# Arduino_Board_rev2.net
KiCad netlist of a schematic drawn in EAGLE
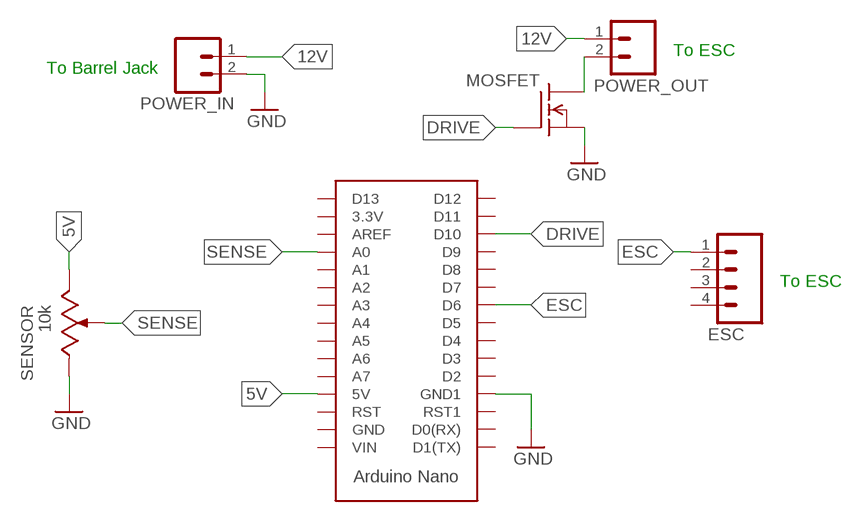
[diagram p0: schematic, sheet 1]

(export (version "E")
  (design (tool "Eeschema 10.0.6"))
  (components
    (comp (ref "ESC")
      (value "M04")
      (footprint "eagle-import:1X04")
      (libsource (lib "eagle-import") (part "M04"))
    )
    (comp (ref "MOSFET")
      (value "SI2312")
      (footprint "eagle-import:SOT-23")
      (libsource (lib "eagle-import") (part "SI2312"))
    )
    (comp (ref "POWER_IN")
      (value "M02")
      (footprint "eagle-import:1X02")
      (libsource (lib "eagle-import") (part "M02"))
    )
    (comp (ref "POWER_OUT")
      (value "M02")
      (footprint "eagle-import:1X02")
      (libsource (lib "eagle-import") (part "M02"))
    )
    (comp (ref "SENSOR")
      (value "10k")
      (footprint "eagle-import:SV03A")
      (libsource (lib "eagle-import") (part "SV03"))
    )
    (comp (ref "U$1")
      (value "ARDUINO_NANO")
      (footprint "eagle-import:ARDUINO_NANO")
      (libsource (lib "eagle-import") (part "ARDUINO_NANO"))
    )
  )
  (nets
    (net (code "1") (name "5V") (class "Default")
      (node (ref "SENSOR") (pin "3") (pinfunction "A_3") (pintype "passive"))
      (node (ref "U$1") (pin "5V") (pinfunction "5V_5V") (pintype "bidirectional"))
    )
    (net (code "2") (name "12V") (class "Default")
      (node (ref "POWER_IN") (pin "1") (pinfunction "1_1") (pintype "passive"))
      (node (ref "POWER_OUT") (pin "1") (pinfunction "1_1") (pintype "passive"))
    )
    (net (code "3") (name "DRIVE") (class "Default")
      (node (ref "MOSFET") (pin "1") (pinfunction "G_1") (pintype "passive"))
      (node (ref "U$1") (pin "D10") (pinfunction "D10_D10") (pintype "bidirectional"))
    )
    (net (code "4") (name "ESC") (class "Default")
      (node (ref "ESC") (pin "1") (pinfunction "1_1") (pintype "passive"))
      (node (ref "U$1") (pin "D6") (pinfunction "D6_D6") (pintype "bidirectional"))
    )
    (net (code "5") (name "GND") (class "Default")
      (node (ref "MOSFET") (pin "2") (pinfunction "S_2") (pintype "passive"))
      (node (ref "POWER_IN") (pin "2") (pinfunction "2_2") (pintype "passive"))
      (node (ref "SENSOR") (pin "1") (pinfunction "E_1") (pintype "passive"))
      (node (ref "U$1") (pin "GND1") (pinfunction "GND1_GND1") (pintype "bidirectional"))
    )
    (net (code "6") (name "Net-(MOSFET-D)") (class "Default")
      (node (ref "MOSFET") (pin "3") (pinfunction "D_3") (pintype "passive"))
      (node (ref "POWER_OUT") (pin "2") (pinfunction "2_2") (pintype "passive"))
    )
    (net (code "7") (name "SENSE") (class "Default")
      (node (ref "SENSOR") (pin "2") (pinfunction "S_2") (pintype "passive"))
      (node (ref "SENSOR") (pin "2.1") (pinfunction "S_2.1") (pintype "passive"))
      (node (ref "U$1") (pin "A0") (pinfunction "A0_A0") (pintype "bidirectional"))
    )
    (net (code "8") (name "unconnected-(ESC-Pad2)") (class "Default")
      (node (ref "ESC") (pin "2") (pinfunction "2_2") (pintype "passive"))
    )
    (net (code "9") (name "unconnected-(ESC-Pad3)") (class "Default")
      (node (ref "ESC") (pin "3") (pinfunction "3_3") (pintype "passive"))
    )
    (net (code "10") (name "unconnected-(ESC-Pad4)") (class "Default")
      (node (ref "ESC") (pin "4") (pinfunction "4_4") (pintype "passive"))
    )
    (net (code "11") (name "unconnected-(U$1-Pad3.3V)") (class "Default")
      (node (ref "U$1") (pin "3.3V") (pinfunction "3.3V_3.3V") (pintype "bidirectional"))
    )
    (net (code "12") (name "unconnected-(U$1-PadA1)") (class "Default")
      (node (ref "U$1") (pin "A1") (pinfunction "A1_A1") (pintype "bidirectional"))
    )
    (net (code "13") (name "unconnected-(U$1-PadA2)") (class "Default")
      (node (ref "U$1") (pin "A2") (pinfunction "A2_A2") (pintype "bidirectional"))
    )
    (net (code "14") (name "unconnected-(U$1-PadA3)") (class "Default")
      (node (ref "U$1") (pin "A3") (pinfunction "A3_A3") (pintype "bidirectional"))
    )
    (net (code "15") (name "unconnected-(U$1-PadA4)") (class "Default")
      (node (ref "U$1") (pin "A4") (pinfunction "A4_A4") (pintype "bidirectional"))
    )
    (net (code "16") (name "unconnected-(U$1-PadA5)") (class "Default")
      (node (ref "U$1") (pin "A5") (pinfunction "A5_A5") (pintype "bidirectional"))
    )
    (net (code "17") (name "unconnected-(U$1-PadA6)") (class "Default")
      (node (ref "U$1") (pin "A6") (pinfunction "A6_A6") (pintype "bidirectional"))
    )
    (net (code "18") (name "unconnected-(U$1-PadA7)") (class "Default")
      (node (ref "U$1") (pin "A7") (pinfunction "A7_A7") (pintype "bidirectional"))
    )
    (net (code "19") (name "unconnected-(U$1-PadAREF)") (class "Default")
      (node (ref "U$1") (pin "AREF") (pinfunction "AREF_AREF") (pintype "bidirectional"))
    )
    (net (code "20") (name "unconnected-(U$1-PadD0(RX))") (class "Default")
      (node (ref "U$1") (pin "D0(RX)") (pinfunction "D0(RX)_D0(RX)") (pintype "bidirectional"))
    )
    (net (code "21") (name "unconnected-(U$1-PadD1(TX))") (class "Default")
      (node (ref "U$1") (pin "D1(TX)") (pinfunction "D1(TX)_D1(TX)") (pintype "bidirectional"))
    )
    (net (code "22") (name "unconnected-(U$1-PadD2)") (class "Default")
      (node (ref "U$1") (pin "D2") (pinfunction "D2_D2") (pintype "bidirectional"))
    )
    (net (code "23") (name "unconnected-(U$1-PadD3)") (class "Default")
      (node (ref "U$1") (pin "D3") (pinfunction "D3_D3") (pintype "bidirectional"))
    )
    (net (code "24") (name "unconnected-(U$1-PadD4)") (class "Default")
      (node (ref "U$1") (pin "D4") (pinfunction "D4_D4") (pintype "bidirectional"))
    )
    (net (code "25") (name "unconnected-(U$1-PadD5)") (class "Default")
      (node (ref "U$1") (pin "D5") (pinfunction "D5_D5") (pintype "bidirectional"))
    )
    (net (code "26") (name "unconnected-(U$1-PadD7)") (class "Default")
      (node (ref "U$1") (pin "D7") (pinfunction "D7_D7") (pintype "bidirectional"))
    )
    (net (code "27") (name "unconnected-(U$1-PadD8)") (class "Default")
      (node (ref "U$1") (pin "D8") (pinfunction "D8_D8") (pintype "bidirectional"))
    )
    (net (code "28") (name "unconnected-(U$1-PadD9)") (class "Default")
      (node (ref "U$1") (pin "D9") (pinfunction "D9_D9") (pintype "bidirectional"))
    )
    (net (code "29") (name "unconnected-(U$1-PadD11)") (class "Default")
      (node (ref "U$1") (pin "D11") (pinfunction "D11_D11") (pintype "bidirectional"))
    )
    (net (code "30") (name "unconnected-(U$1-PadD12)") (class "Default")
      (node (ref "U$1") (pin "D12") (pinfunction "D12_D12") (pintype "bidirectional"))
    )
    (net (code "31") (name "unconnected-(U$1-PadD13)") (class "Default")
      (node (ref "U$1") (pin "D13") (pinfunction "D13_D13") (pintype "bidirectional"))
    )
    (net (code "32") (name "unconnected-(U$1-PadGND)") (class "Default")
      (node (ref "U$1") (pin "GND") (pinfunction "GND_GND") (pintype "bidirectional"))
    )
    (net (code "33") (name "unconnected-(U$1-PadRST)") (class "Default")
      (node (ref "U$1") (pin "RST") (pinfunction "RST_RST") (pintype "bidirectional"))
    )
    (net (code "34") (name "unconnected-(U$1-PadRST1)") (class "Default")
      (node (ref "U$1") (pin "RST1") (pinfunction "RST1_RST1") (pintype "bidirectional"))
    )
    (net (code "35") (name "unconnected-(U$1-PadVIN)") (class "Default")
      (node (ref "U$1") (pin "VIN") (pinfunction "VIN_VIN") (pintype "bidirectional"))
    )
  )
)
